# esprog.net
KiCad netlist of a schematic drawn in EAGLE
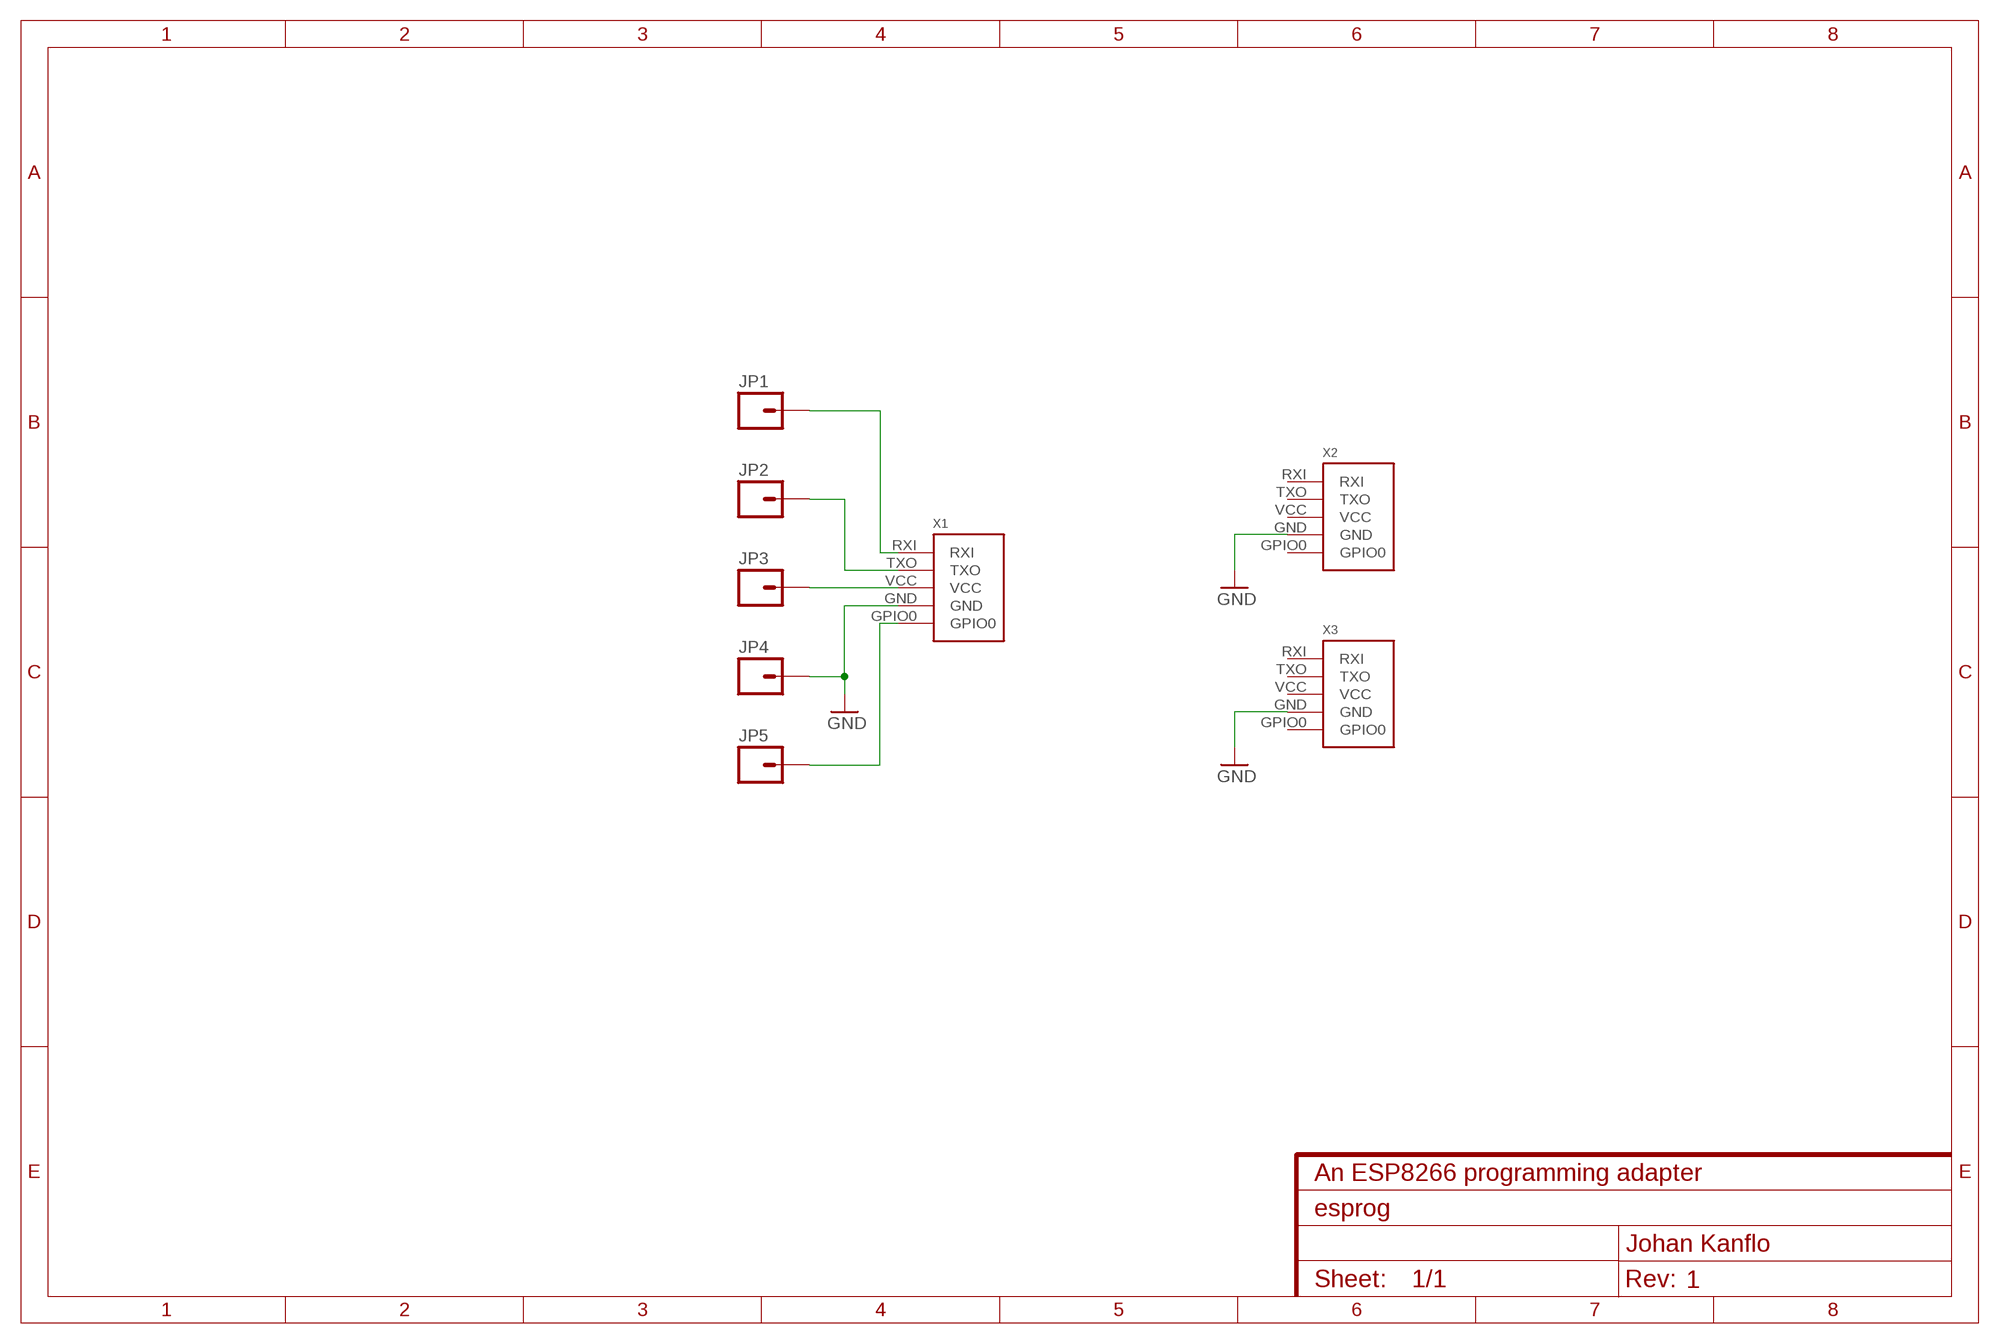
[diagram p0: schematic, sheet 1]

(export (version "E")
  (design (tool "Eeschema 10.0.6"))
  (components
    (comp (ref "JP1")
      (value "M01PTH_NO_SILK_YES_STOP")
      (footprint "eagle-import:1X01_NO_SILK")
      (libsource (lib "eagle-import") (part "M01PTH_NO_SILK_YES_STOP"))
    )
    (comp (ref "JP2")
      (value "M01PTH_NO_SILK_YES_STOP")
      (footprint "eagle-import:1X01_NO_SILK")
      (libsource (lib "eagle-import") (part "M01PTH_NO_SILK_YES_STOP"))
    )
    (comp (ref "JP3")
      (value "M01PTH_NO_SILK_YES_STOP")
      (footprint "eagle-import:1X01_NO_SILK")
      (libsource (lib "eagle-import") (part "M01PTH_NO_SILK_YES_STOP"))
    )
    (comp (ref "JP4")
      (value "M01PTH_NO_SILK_YES_STOP")
      (footprint "eagle-import:1X01_NO_SILK")
      (libsource (lib "eagle-import") (part "M01PTH_NO_SILK_YES_STOP"))
    )
    (comp (ref "JP5")
      (value "M01PTH_NO_SILK_YES_STOP")
      (footprint "eagle-import:1X01_NO_SILK")
      (libsource (lib "eagle-import") (part "M01PTH_NO_SILK_YES_STOP"))
    )
    (comp (ref "X1")
      (value "ESPROGESPROG-CONNECTOR")
      (footprint "eagle-import:ESPROG-TH")
      (libsource (lib "eagle-import") (part "ESPROGESPROG-CONNECTOR"))
    )
    (comp (ref "X2")
      (value "ESPROGESPROG-CONNECTOR")
      (footprint "eagle-import:ESPROG-TH")
      (libsource (lib "eagle-import") (part "ESPROGESPROG-CONNECTOR"))
    )
    (comp (ref "X3")
      (value "ESPROGESPROG-CONNECTOR")
      (footprint "eagle-import:ESPROG-TH")
      (libsource (lib "eagle-import") (part "ESPROGESPROG-CONNECTOR"))
    )
  )
  (nets
    (net (code "1") (name "GND") (class "Default")
      (node (ref "JP4") (pin "1") (pinfunction "1_1") (pintype "passive"))
      (node (ref "X1") (pin "GND") (pinfunction "GND_GND") (pintype "bidirectional"))
      (node (ref "X2") (pin "GND") (pinfunction "GND_GND") (pintype "bidirectional"))
      (node (ref "X3") (pin "GND") (pinfunction "GND_GND") (pintype "bidirectional"))
    )
    (net (code "2") (name "Net-(JP1-Pad1)") (class "Default")
      (node (ref "JP1") (pin "1") (pinfunction "1_1") (pintype "passive"))
      (node (ref "X1") (pin "RXI") (pinfunction "RXI_RXI") (pintype "bidirectional"))
    )
    (net (code "3") (name "Net-(JP2-Pad1)") (class "Default")
      (node (ref "JP2") (pin "1") (pinfunction "1_1") (pintype "passive"))
      (node (ref "X1") (pin "TXO") (pinfunction "TXO_TXO") (pintype "bidirectional"))
    )
    (net (code "4") (name "Net-(JP3-Pad1)") (class "Default")
      (node (ref "JP3") (pin "1") (pinfunction "1_1") (pintype "passive"))
      (node (ref "X1") (pin "VCC") (pinfunction "VCC_VCC") (pintype "bidirectional"))
    )
    (net (code "5") (name "Net-(JP5-Pad1)") (class "Default")
      (node (ref "JP5") (pin "1") (pinfunction "1_1") (pintype "passive"))
      (node (ref "X1") (pin "GPIO0") (pinfunction "GPIO0_GPIO0") (pintype "bidirectional"))
    )
    (net (code "6") (name "unconnected-(X2-PadGPIO0)") (class "Default")
      (node (ref "X2") (pin "GPIO0") (pinfunction "GPIO0_GPIO0") (pintype "bidirectional"))
    )
    (net (code "7") (name "unconnected-(X2-PadRXI)") (class "Default")
      (node (ref "X2") (pin "RXI") (pinfunction "RXI_RXI") (pintype "bidirectional"))
    )
    (net (code "8") (name "unconnected-(X2-PadTXO)") (class "Default")
      (node (ref "X2") (pin "TXO") (pinfunction "TXO_TXO") (pintype "bidirectional"))
    )
    (net (code "9") (name "unconnected-(X2-PadVCC)") (class "Default")
      (node (ref "X2") (pin "VCC") (pinfunction "VCC_VCC") (pintype "bidirectional"))
    )
    (net (code "10") (name "unconnected-(X3-PadGPIO0)") (class "Default")
      (node (ref "X3") (pin "GPIO0") (pinfunction "GPIO0_GPIO0") (pintype "bidirectional"))
    )
    (net (code "11") (name "unconnected-(X3-PadRXI)") (class "Default")
      (node (ref "X3") (pin "RXI") (pinfunction "RXI_RXI") (pintype "bidirectional"))
    )
    (net (code "12") (name "unconnected-(X3-PadTXO)") (class "Default")
      (node (ref "X3") (pin "TXO") (pinfunction "TXO_TXO") (pintype "bidirectional"))
    )
    (net (code "13") (name "unconnected-(X3-PadVCC)") (class "Default")
      (node (ref "X3") (pin "VCC") (pinfunction "VCC_VCC") (pintype "bidirectional"))
    )
  )
)
